# RC_Car_Project_Slave.net
KiCad netlist of a schematic drawn in EasyEDA
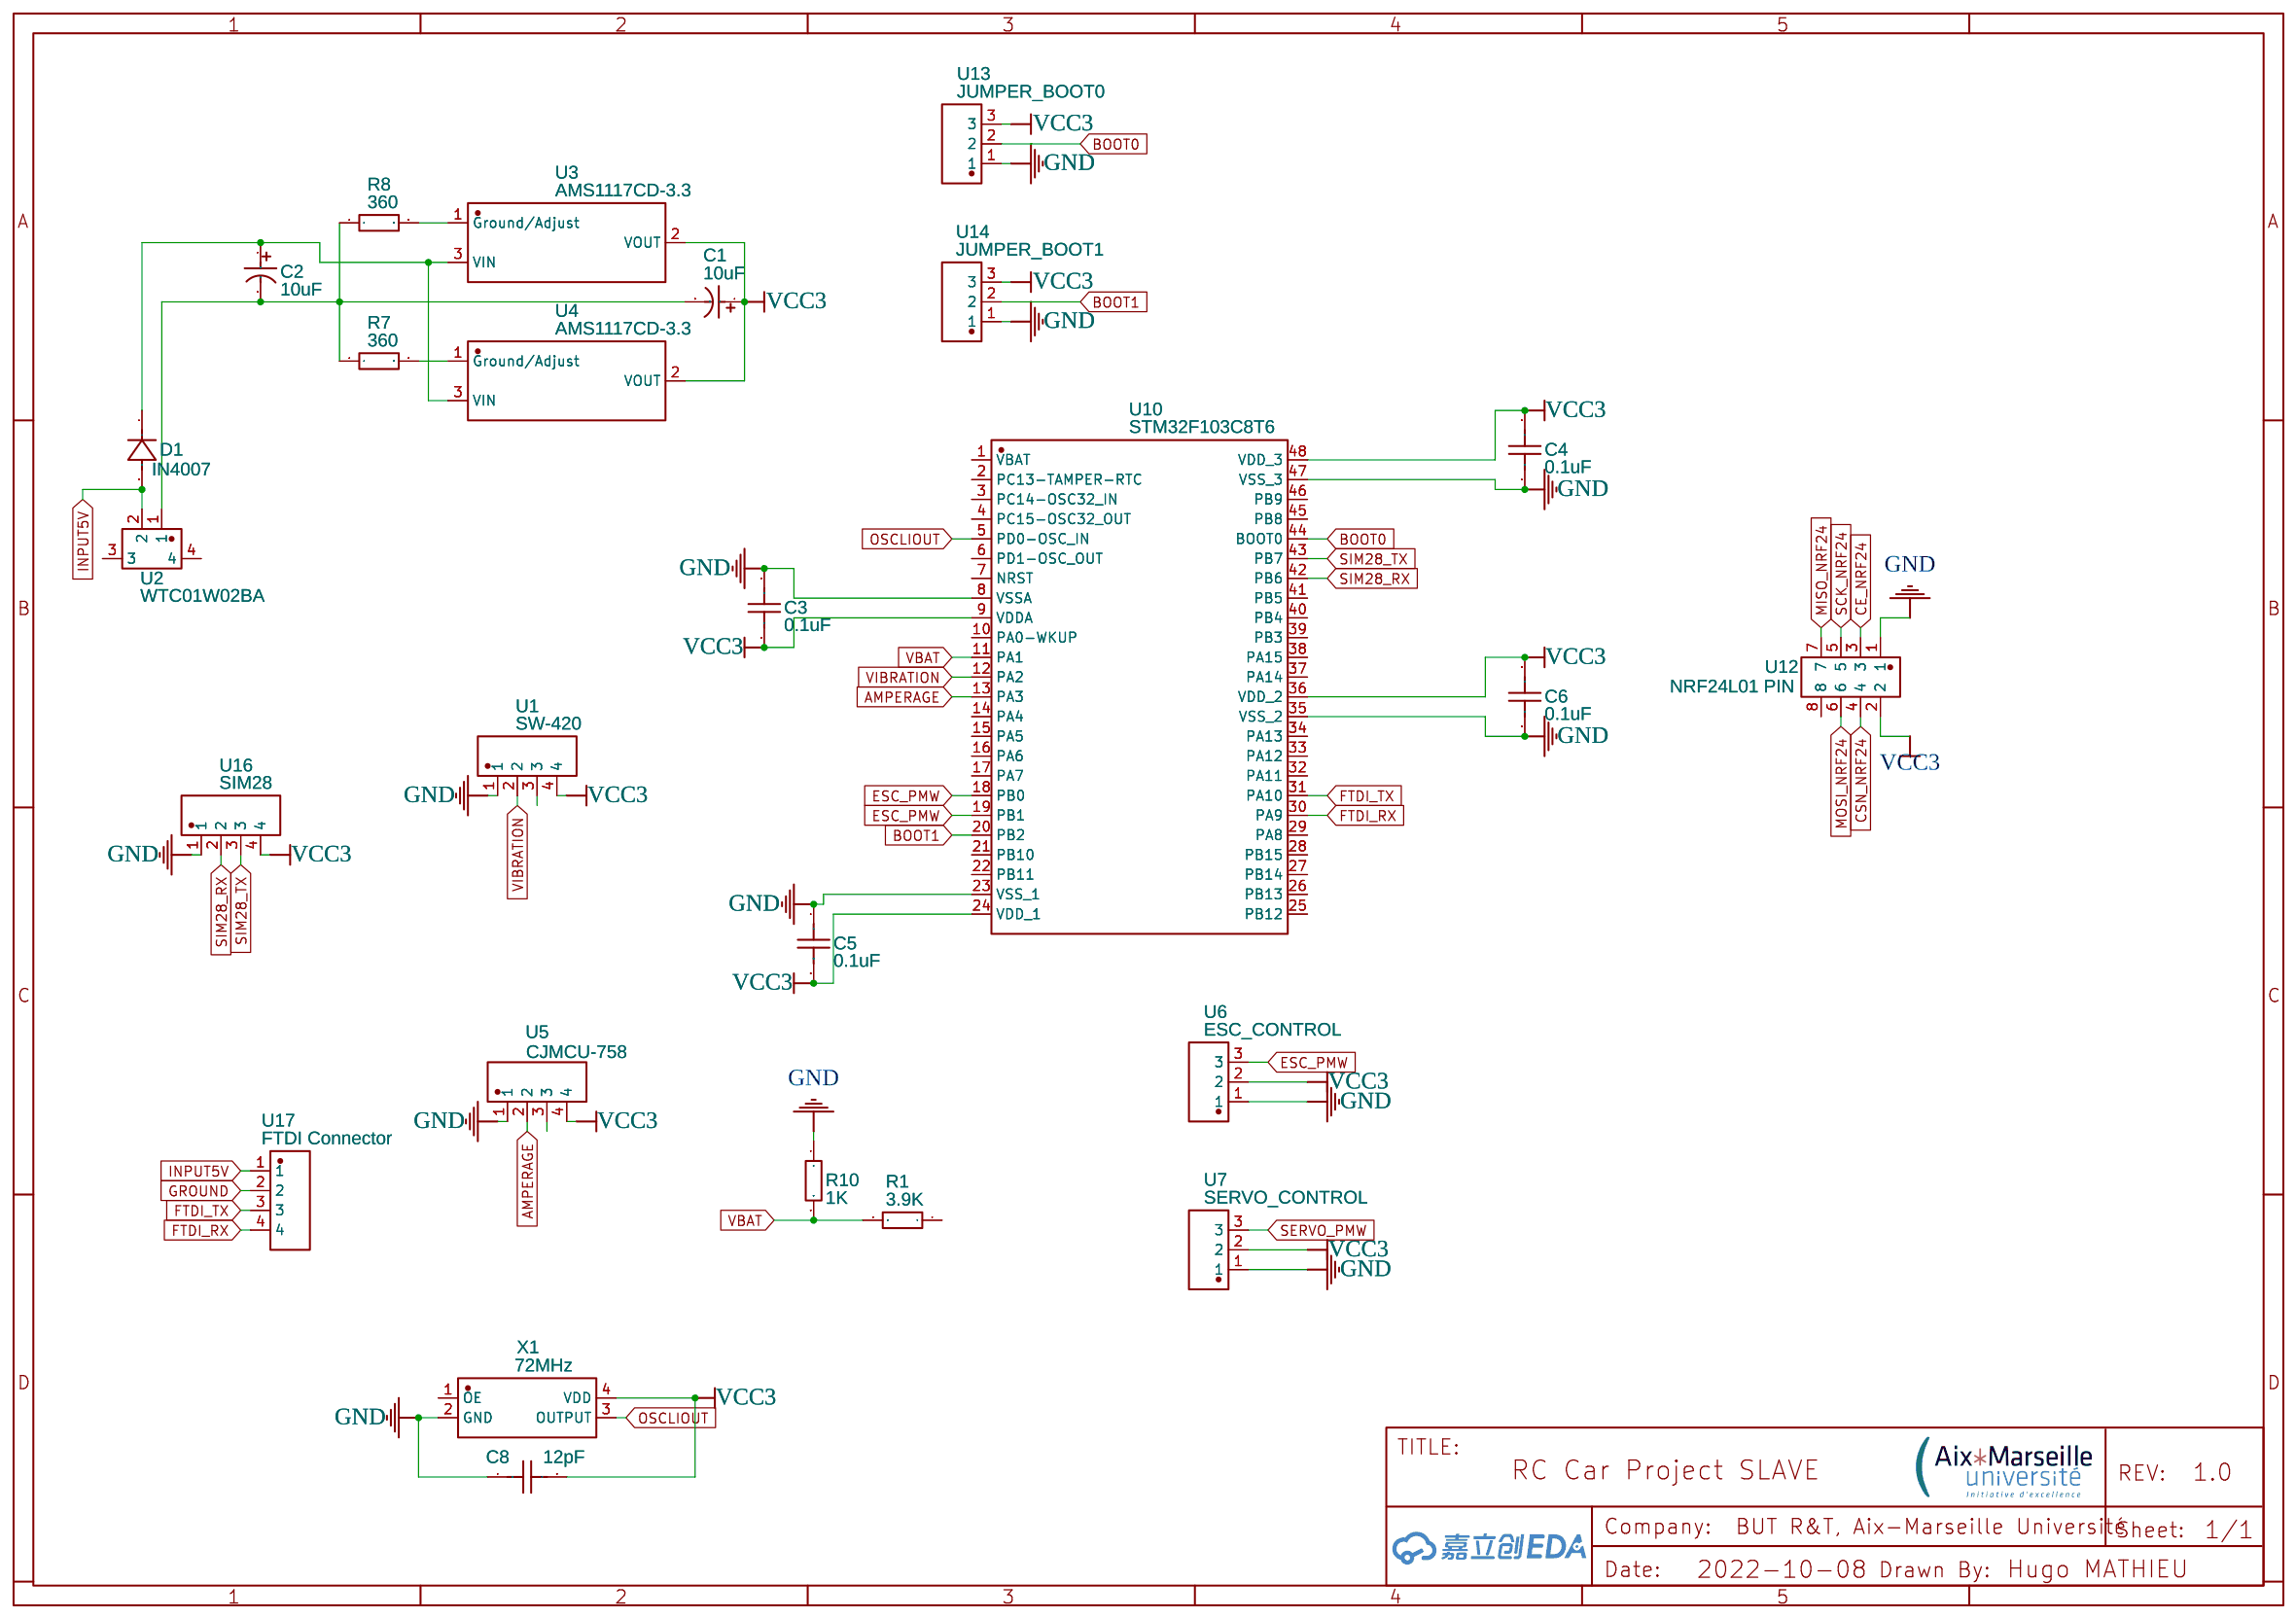
[diagram p0: schematic sheet]

(export (version "E")
  (design (tool "Eeschema 10.0.6"))
  (components
    (comp (ref "C1")
      (value "10uF")
      (fields
        (field (name "BOM_Manufacturer Part") "RVT1H100M0505")
        (field (name "BOM_Supplier Part") "C72487")
      )
      (libsource (lib "") (part "RVT1H100M0505"))
    )
    (comp (ref "C2")
      (value "10uF")
      (fields
        (field (name "BOM_Manufacturer Part") "RVT1H100M0505")
        (field (name "BOM_Supplier Part") "C72487")
      )
      (libsource (lib "") (part "RVT1H100M0505_1"))
    )
    (comp (ref "C3")
      (value "0.1uF")
      (fields
        (field (name "BOM_Manufacturer Part") "AC0805JRNPO9BN220")
        (field (name "BOM_Supplier Part") "C149614")
      )
      (libsource (lib "") (part "AC0805JRNPO9BN220_2"))
    )
    (comp (ref "C4")
      (value "0.1uF")
      (fields
        (field (name "BOM_Manufacturer Part") "AC0805JRNPO9BN220")
        (field (name "BOM_Supplier Part") "C149614")
      )
      (libsource (lib "") (part "AC0805JRNPO9BN220"))
    )
    (comp (ref "C5")
      (value "0.1uF")
      (fields
        (field (name "BOM_Manufacturer Part") "AC0805JRNPO9BN220")
        (field (name "BOM_Supplier Part") "C149614")
      )
      (libsource (lib "") (part "AC0805JRNPO9BN220_2"))
    )
    (comp (ref "C6")
      (value "0.1uF")
      (fields
        (field (name "BOM_Manufacturer Part") "AC0805JRNPO9BN220")
        (field (name "BOM_Supplier Part") "C149614")
      )
      (libsource (lib "") (part "AC0805JRNPO9BN220"))
    )
    (comp (ref "C8")
      (value "12pF")
      (fields
        (field (name "BOM_Manufacturer Part") "AC0805JRNPO9BN220")
        (field (name "BOM_Supplier Part") "C149614")
      )
      (libsource (lib "") (part "AC0805JRNPO9BN220_1"))
    )
    (comp (ref "D1")
      (value "IN4007")
      (fields (field (name "BOM_Supplier Part") "C9900004719"))
      (libsource (lib "") (part "IN4007"))
    )
    (comp (ref "R1")
      (value "3.9K")
      (fields
        (field (name "BOM_Manufacturer Part") "RC0805FR-07100RL")
        (field (name "BOM_Supplier Part") "C105577")
      )
      (libsource (lib "") (part "RC0805FR-07100RL_2"))
    )
    (comp (ref "R7")
      (value "360")
      (fields
        (field (name "BOM_Manufacturer Part") "RC0805FR-07100RL")
        (field (name "BOM_Supplier Part") "C105577")
      )
      (libsource (lib "") (part "RC0805FR-07100RL_1"))
    )
    (comp (ref "R8")
      (value "360")
      (fields
        (field (name "BOM_Manufacturer Part") "RC0805FR-07100RL")
        (field (name "BOM_Supplier Part") "C105577")
      )
      (libsource (lib "") (part "RC0805FR-07100RL_1"))
    )
    (comp (ref "R10")
      (value "1K")
      (fields
        (field (name "BOM_Manufacturer Part") "RC0805FR-07100RL")
        (field (name "BOM_Supplier Part") "C105577")
      )
      (libsource (lib "") (part "RC0805FR-07100RL"))
    )
    (comp (ref "U1")
      (value "SW-420")
      (fields
        (field (name "BOM_Manufacturer Part") "2.54*4单排")
        (field (name "BOM_Supplier Part") "C9900016163")
      )
      (libsource (lib "") (part "2.54*4单排_1"))
    )
    (comp (ref "U2")
      (value "WTC01W02BA")
      (fields (field (name "BOM_Supplier Part") "C5120226"))
      (libsource (lib "") (part "WTC01W02BA"))
    )
    (comp (ref "U3")
      (value "AMS1117CD-3.3")
      (fields (field (name "BOM_Supplier Part") "C841796"))
      (libsource (lib "") (part "AMS1117CD-3.3"))
    )
    (comp (ref "U4")
      (value "AMS1117CD-3.3")
      (fields (field (name "BOM_Supplier Part") "C841796"))
      (libsource (lib "") (part "AMS1117CD-3.3"))
    )
    (comp (ref "U5")
      (value "CJMCU-758")
      (fields
        (field (name "BOM_Manufacturer Part") "2.54*4单排")
        (field (name "BOM_Supplier Part") "C9900016163")
      )
      (libsource (lib "") (part "2.54*4单排_1"))
    )
    (comp (ref "U6")
      (value "ESC_CONTROL")
      (fields
        (field (name "BOM_Manufacturer Part") "2.54*3单排")
        (field (name "BOM_Supplier Part") "C9900016162")
      )
      (libsource (lib "") (part "2.54*3单排"))
    )
    (comp (ref "U7")
      (value "SERVO_CONTROL")
      (fields
        (field (name "BOM_Manufacturer Part") "2.54*3单排")
        (field (name "BOM_Supplier Part") "C9900016162")
      )
      (libsource (lib "") (part "2.54*3单排"))
    )
    (comp (ref "U10")
      (value "STM32F103C8T6")
      (fields (field (name "BOM_Supplier Part") "C8734"))
      (libsource (lib "") (part "STM32F103C8T6"))
    )
    (comp (ref "U12")
      (value "NRF24L01 PIN")
      (fields (field (name "BOM_Manufacturer Part") "2.54-2*4") (field (name "BOM_Supplier Part") "C2977588"))
      (libsource (lib "") (part "2.54-2*4"))
    )
    (comp (ref "U13")
      (value "JUMPER_BOOT0")
      (fields
        (field (name "BOM_Manufacturer Part") "2.54*3单排")
        (field (name "BOM_Supplier Part") "C9900016162")
      )
      (libsource (lib "") (part "2.54*3单排"))
    )
    (comp (ref "U14")
      (value "JUMPER_BOOT1")
      (fields
        (field (name "BOM_Manufacturer Part") "2.54*3单排")
        (field (name "BOM_Supplier Part") "C9900016162")
      )
      (libsource (lib "") (part "2.54*3单排"))
    )
    (comp (ref "U16")
      (value "SIM28")
      (fields
        (field (name "BOM_Manufacturer Part") "2.54*4单排")
        (field (name "BOM_Supplier Part") "C9900016163")
      )
      (libsource (lib "") (part "2.54*4单排_1"))
    )
    (comp (ref "U17")
      (value "FTDI Connector")
      (fields
        (field (name "BOM_Manufacturer Part") "2.54*4单排")
        (field (name "BOM_Supplier Part") "C9900016163")
      )
      (libsource (lib "") (part "2.54*4单排"))
    )
    (comp (ref "X1")
      (value "72MHz")
      (fields
        (field (name "BOM_Manufacturer Part") "S5D13.560000A20F30T")
        (field (name "BOM_Supplier Part") "C387226")
      )
      (libsource (lib "") (part "S5D13.560000A20F30T"))
    )
  )
  (nets
    (net (code "1") (name "AMPERAGE") (class "Default")
      (node (ref "U10") (pin "13") (pinfunction "PA3_13") (pintype "unspecified"))
      (node (ref "U5") (pin "2") (pinfunction "2_2") (pintype "unspecified"))
    )
    (net (code "2") (name "BOOT0") (class "Default")
      (node (ref "U10") (pin "44") (pinfunction "BOOT0_44") (pintype "unspecified"))
      (node (ref "U13") (pin "2") (pinfunction "2_2") (pintype "unspecified"))
    )
    (net (code "3") (name "BOOT1") (class "Default")
      (node (ref "U10") (pin "20") (pinfunction "PB2_20") (pintype "unspecified"))
      (node (ref "U14") (pin "2") (pinfunction "2_2") (pintype "unspecified"))
    )
    (net (code "4") (name "CE_NRF24") (class "Default")
      (node (ref "U12") (pin "3") (pinfunction "3_3") (pintype "unspecified"))
    )
    (net (code "5") (name "CSN_NRF24") (class "Default")
      (node (ref "U12") (pin "4") (pinfunction "4_4") (pintype "unspecified"))
    )
    (net (code "6") (name "ESC_PMW") (class "Default")
      (node (ref "U10") (pin "18") (pinfunction "PB0_18") (pintype "unspecified"))
      (node (ref "U10") (pin "19") (pinfunction "PB1_19") (pintype "unspecified"))
      (node (ref "U6") (pin "3") (pinfunction "3_3") (pintype "unspecified"))
    )
    (net (code "7") (name "FTDI_RX") (class "Default")
      (node (ref "U10") (pin "30") (pinfunction "PA9_30") (pintype "unspecified"))
      (node (ref "U17") (pin "4") (pinfunction "4_4") (pintype "unspecified"))
    )
    (net (code "8") (name "FTDI_TX") (class "Default")
      (node (ref "U10") (pin "31") (pinfunction "PA10_31") (pintype "unspecified"))
      (node (ref "U17") (pin "3") (pinfunction "3_3") (pintype "unspecified"))
    )
    (net (code "9") (name "GND") (class "Default")
      (node (ref "C3") (pin "1") (pinfunction "1_1") (pintype "unspecified"))
      (node (ref "C4") (pin "1") (pinfunction "1_1") (pintype "unspecified"))
      (node (ref "C5") (pin "1") (pinfunction "1_1") (pintype "unspecified"))
      (node (ref "C6") (pin "1") (pinfunction "1_1") (pintype "unspecified"))
      (node (ref "C8") (pin "1") (pinfunction "1_1") (pintype "unspecified"))
      (node (ref "R10") (pin "1") (pinfunction "1_1") (pintype "input"))
      (node (ref "U1") (pin "1") (pinfunction "1_1") (pintype "unspecified"))
      (node (ref "U10") (pin "23") (pinfunction "VSS_1_23") (pintype "unspecified"))
      (node (ref "U10") (pin "35") (pinfunction "VSS_2_35") (pintype "unspecified"))
      (node (ref "U10") (pin "47") (pinfunction "VSS_3_47") (pintype "unspecified"))
      (node (ref "U10") (pin "8") (pinfunction "VSSA_8") (pintype "unspecified"))
      (node (ref "U12") (pin "1") (pinfunction "1_1") (pintype "unspecified"))
      (node (ref "U13") (pin "1") (pinfunction "1_1") (pintype "unspecified"))
      (node (ref "U14") (pin "1") (pinfunction "1_1") (pintype "unspecified"))
      (node (ref "U16") (pin "1") (pinfunction "1_1") (pintype "unspecified"))
      (node (ref "U5") (pin "1") (pinfunction "1_1") (pintype "unspecified"))
      (node (ref "U6") (pin "1") (pinfunction "1_1") (pintype "unspecified"))
      (node (ref "U7") (pin "1") (pinfunction "1_1") (pintype "unspecified"))
      (node (ref "X1") (pin "2") (pinfunction "GND_2") (pintype "unspecified"))
    )
    (net (code "10") (name "GROUND") (class "Default")
      (node (ref "U17") (pin "2") (pinfunction "2_2") (pintype "unspecified"))
    )
    (net (code "11") (name "INPUT5V") (class "Default")
      (node (ref "D1") (pin "2") (pinfunction "A_2") (pintype "unspecified"))
      (node (ref "U17") (pin "1") (pinfunction "1_1") (pintype "unspecified"))
      (node (ref "U2") (pin "2") (pinfunction "2_2") (pintype "unspecified"))
    )
    (net (code "12") (name "MISO_NRF24") (class "Default")
      (node (ref "U12") (pin "7") (pinfunction "7_7") (pintype "unspecified"))
    )
    (net (code "13") (name "MOSI_NRF24") (class "Default")
      (node (ref "U12") (pin "6") (pinfunction "6_6") (pintype "unspecified"))
    )
    (net (code "14") (name "Net-(C1-Pad2)") (class "Default")
      (node (ref "C1") (pin "2") (pinfunction "2_2") (pintype "input"))
      (node (ref "C2") (pin "2") (pinfunction "2_2") (pintype "input"))
      (node (ref "R7") (pin "1") (pinfunction "1_1") (pintype "input"))
      (node (ref "R8") (pin "1") (pinfunction "1_1") (pintype "input"))
      (node (ref "U2") (pin "1") (pinfunction "1_1") (pintype "unspecified"))
    )
    (net (code "15") (name "Net-(D1-K)") (class "Default")
      (node (ref "C2") (pin "1") (pinfunction "1_1") (pintype "input"))
      (node (ref "D1") (pin "1") (pinfunction "K_1") (pintype "unspecified"))
      (node (ref "U3") (pin "3") (pinfunction "VIN_3") (pintype "unspecified"))
      (node (ref "U4") (pin "3") (pinfunction "VIN_3") (pintype "unspecified"))
    )
    (net (code "16") (name "Net-(U3-Ground{slash}Adjust)") (class "Default")
      (node (ref "R8") (pin "2") (pinfunction "2_2") (pintype "input"))
      (node (ref "U3") (pin "1") (pinfunction "Ground/Adjust_1") (pintype "unspecified"))
    )
    (net (code "17") (name "Net-(U4-Ground{slash}Adjust)") (class "Default")
      (node (ref "R7") (pin "2") (pinfunction "2_2") (pintype "input"))
      (node (ref "U4") (pin "1") (pinfunction "Ground/Adjust_1") (pintype "unspecified"))
    )
    (net (code "18") (name "OSCLIOUT") (class "Default")
      (node (ref "U10") (pin "5") (pinfunction "PD0-OSC_IN_5") (pintype "unspecified"))
      (node (ref "X1") (pin "3") (pinfunction "OUTPUT_3") (pintype "unspecified"))
    )
    (net (code "19") (name "SCK_NRF24") (class "Default")
      (node (ref "U12") (pin "5") (pinfunction "5_5") (pintype "unspecified"))
    )
    (net (code "20") (name "SERVO_PMW") (class "Default")
      (node (ref "U7") (pin "3") (pinfunction "3_3") (pintype "unspecified"))
    )
    (net (code "21") (name "SIM28_RX") (class "Default")
      (node (ref "U10") (pin "42") (pinfunction "PB6_42") (pintype "unspecified"))
      (node (ref "U16") (pin "2") (pinfunction "2_2") (pintype "unspecified"))
    )
    (net (code "22") (name "SIM28_TX") (class "Default")
      (node (ref "U10") (pin "43") (pinfunction "PB7_43") (pintype "unspecified"))
      (node (ref "U16") (pin "3") (pinfunction "3_3") (pintype "unspecified"))
    )
    (net (code "23") (name "VBAT") (class "Default")
      (node (ref "R1") (pin "2") (pinfunction "2_2") (pintype "input"))
      (node (ref "R10") (pin "2") (pinfunction "2_2") (pintype "input"))
      (node (ref "U10") (pin "11") (pinfunction "PA1_11") (pintype "unspecified"))
    )
    (net (code "24") (name "VCC3") (class "Default")
      (node (ref "C1") (pin "1") (pinfunction "1_1") (pintype "input"))
      (node (ref "C3") (pin "2") (pinfunction "2_2") (pintype "unspecified"))
      (node (ref "C4") (pin "2") (pinfunction "2_2") (pintype "unspecified"))
      (node (ref "C5") (pin "2") (pinfunction "2_2") (pintype "unspecified"))
      (node (ref "C6") (pin "2") (pinfunction "2_2") (pintype "unspecified"))
      (node (ref "C8") (pin "2") (pinfunction "2_2") (pintype "unspecified"))
      (node (ref "U1") (pin "4") (pinfunction "4_4") (pintype "unspecified"))
      (node (ref "U10") (pin "24") (pinfunction "VDD_1_24") (pintype "unspecified"))
      (node (ref "U10") (pin "36") (pinfunction "VDD_2_36") (pintype "unspecified"))
      (node (ref "U10") (pin "48") (pinfunction "VDD_3_48") (pintype "unspecified"))
      (node (ref "U10") (pin "9") (pinfunction "VDDA_9") (pintype "unspecified"))
      (node (ref "U12") (pin "2") (pinfunction "2_2") (pintype "unspecified"))
      (node (ref "U13") (pin "3") (pinfunction "3_3") (pintype "unspecified"))
      (node (ref "U14") (pin "3") (pinfunction "3_3") (pintype "unspecified"))
      (node (ref "U16") (pin "4") (pinfunction "4_4") (pintype "unspecified"))
      (node (ref "U3") (pin "2") (pinfunction "VOUT_2") (pintype "unspecified"))
      (node (ref "U4") (pin "2") (pinfunction "VOUT_2") (pintype "unspecified"))
      (node (ref "U5") (pin "4") (pinfunction "4_4") (pintype "unspecified"))
      (node (ref "U6") (pin "2") (pinfunction "2_2") (pintype "unspecified"))
      (node (ref "U7") (pin "2") (pinfunction "2_2") (pintype "unspecified"))
      (node (ref "X1") (pin "4") (pinfunction "VDD_4") (pintype "unspecified"))
    )
    (net (code "25") (name "VIBRATION") (class "Default")
      (node (ref "U1") (pin "2") (pinfunction "2_2") (pintype "unspecified"))
      (node (ref "U10") (pin "12") (pinfunction "PA2_12") (pintype "unspecified"))
    )
    (net (code "26") (name "unconnected-(R1-Pad1)") (class "Default")
      (node (ref "R1") (pin "1") (pinfunction "1_1") (pintype "input"))
    )
    (net (code "27") (name "unconnected-(U1-Pad3)") (class "Default")
      (node (ref "U1") (pin "3") (pinfunction "3_3") (pintype "unspecified"))
    )
    (net (code "28") (name "unconnected-(U2-Pad3)") (class "Default")
      (node (ref "U2") (pin "3") (pinfunction "3_3") (pintype "unspecified"))
    )
    (net (code "29") (name "unconnected-(U2-Pad4)") (class "Default")
      (node (ref "U2") (pin "4") (pinfunction "4_4") (pintype "unspecified"))
    )
    (net (code "30") (name "unconnected-(U5-Pad3)") (class "Default")
      (node (ref "U5") (pin "3") (pinfunction "3_3") (pintype "unspecified"))
    )
    (net (code "31") (name "unconnected-(U10-NRST-Pad7)") (class "Default")
      (node (ref "U10") (pin "7") (pinfunction "NRST_7") (pintype "unspecified"))
    )
    (net (code "32") (name "unconnected-(U10-PA0-WKUP-Pad10)") (class "Default")
      (node (ref "U10") (pin "10") (pinfunction "PA0-WKUP_10") (pintype "unspecified"))
    )
    (net (code "33") (name "unconnected-(U10-PA4-Pad14)") (class "Default")
      (node (ref "U10") (pin "14") (pinfunction "PA4_14") (pintype "unspecified"))
    )
    (net (code "34") (name "unconnected-(U10-PA5-Pad15)") (class "Default")
      (node (ref "U10") (pin "15") (pinfunction "PA5_15") (pintype "unspecified"))
    )
    (net (code "35") (name "unconnected-(U10-PA6-Pad16)") (class "Default")
      (node (ref "U10") (pin "16") (pinfunction "PA6_16") (pintype "unspecified"))
    )
    (net (code "36") (name "unconnected-(U10-PA7-Pad17)") (class "Default")
      (node (ref "U10") (pin "17") (pinfunction "PA7_17") (pintype "unspecified"))
    )
    (net (code "37") (name "unconnected-(U10-PA8-Pad29)") (class "Default")
      (node (ref "U10") (pin "29") (pinfunction "PA8_29") (pintype "unspecified"))
    )
    (net (code "38") (name "unconnected-(U10-PA11-Pad32)") (class "Default")
      (node (ref "U10") (pin "32") (pinfunction "PA11_32") (pintype "unspecified"))
    )
    (net (code "39") (name "unconnected-(U10-PA12-Pad33)") (class "Default")
      (node (ref "U10") (pin "33") (pinfunction "PA12_33") (pintype "unspecified"))
    )
    (net (code "40") (name "unconnected-(U10-PA13-Pad34)") (class "Default")
      (node (ref "U10") (pin "34") (pinfunction "PA13_34") (pintype "unspecified"))
    )
    (net (code "41") (name "unconnected-(U10-PA14-Pad37)") (class "Default")
      (node (ref "U10") (pin "37") (pinfunction "PA14_37") (pintype "unspecified"))
    )
    (net (code "42") (name "unconnected-(U10-PA15-Pad38)") (class "Default")
      (node (ref "U10") (pin "38") (pinfunction "PA15_38") (pintype "unspecified"))
    )
    (net (code "43") (name "unconnected-(U10-PB3-Pad39)") (class "Default")
      (node (ref "U10") (pin "39") (pinfunction "PB3_39") (pintype "unspecified"))
    )
    (net (code "44") (name "unconnected-(U10-PB4-Pad40)") (class "Default")
      (node (ref "U10") (pin "40") (pinfunction "PB4_40") (pintype "unspecified"))
    )
    (net (code "45") (name "unconnected-(U10-PB5-Pad41)") (class "Default")
      (node (ref "U10") (pin "41") (pinfunction "PB5_41") (pintype "unspecified"))
    )
    (net (code "46") (name "unconnected-(U10-PB8-Pad45)") (class "Default")
      (node (ref "U10") (pin "45") (pinfunction "PB8_45") (pintype "unspecified"))
    )
    (net (code "47") (name "unconnected-(U10-PB9-Pad46)") (class "Default")
      (node (ref "U10") (pin "46") (pinfunction "PB9_46") (pintype "unspecified"))
    )
    (net (code "48") (name "unconnected-(U10-PB10-Pad21)") (class "Default")
      (node (ref "U10") (pin "21") (pinfunction "PB10_21") (pintype "unspecified"))
    )
    (net (code "49") (name "unconnected-(U10-PB11-Pad22)") (class "Default")
      (node (ref "U10") (pin "22") (pinfunction "PB11_22") (pintype "unspecified"))
    )
    (net (code "50") (name "unconnected-(U10-PB12-Pad25)") (class "Default")
      (node (ref "U10") (pin "25") (pinfunction "PB12_25") (pintype "unspecified"))
    )
    (net (code "51") (name "unconnected-(U10-PB13-Pad26)") (class "Default")
      (node (ref "U10") (pin "26") (pinfunction "PB13_26") (pintype "unspecified"))
    )
    (net (code "52") (name "unconnected-(U10-PB14-Pad27)") (class "Default")
      (node (ref "U10") (pin "27") (pinfunction "PB14_27") (pintype "unspecified"))
    )
    (net (code "53") (name "unconnected-(U10-PB15-Pad28)") (class "Default")
      (node (ref "U10") (pin "28") (pinfunction "PB15_28") (pintype "unspecified"))
    )
    (net (code "54") (name "unconnected-(U10-PC13-TAMPER-RTC-Pad2)") (class "Default")
      (node (ref "U10") (pin "2") (pinfunction "PC13-TAMPER-RTC_2") (pintype "unspecified"))
    )
    (net (code "55") (name "unconnected-(U10-PC14-OSC32_IN-Pad3)") (class "Default")
      (node (ref "U10") (pin "3") (pinfunction "PC14-OSC32_IN_3") (pintype "unspecified"))
    )
    (net (code "56") (name "unconnected-(U10-PC15-OSC32_OUT-Pad4)") (class "Default")
      (node (ref "U10") (pin "4") (pinfunction "PC15-OSC32_OUT_4") (pintype "unspecified"))
    )
    (net (code "57") (name "unconnected-(U10-PD1-OSC_OUT-Pad6)") (class "Default")
      (node (ref "U10") (pin "6") (pinfunction "PD1-OSC_OUT_6") (pintype "unspecified"))
    )
    (net (code "58") (name "unconnected-(U10-VBAT-Pad1)") (class "Default")
      (node (ref "U10") (pin "1") (pinfunction "VBAT_1") (pintype "unspecified"))
    )
    (net (code "59") (name "unconnected-(U12-Pad8)") (class "Default")
      (node (ref "U12") (pin "8") (pinfunction "8_8") (pintype "unspecified"))
    )
    (net (code "60") (name "unconnected-(X1-OE-Pad1)") (class "Default")
      (node (ref "X1") (pin "1") (pinfunction "OE_1") (pintype "unspecified"))
    )
  )
)
